# M_2_CSI2.net
KiCad netlist of a schematic drawn in Altium Designer
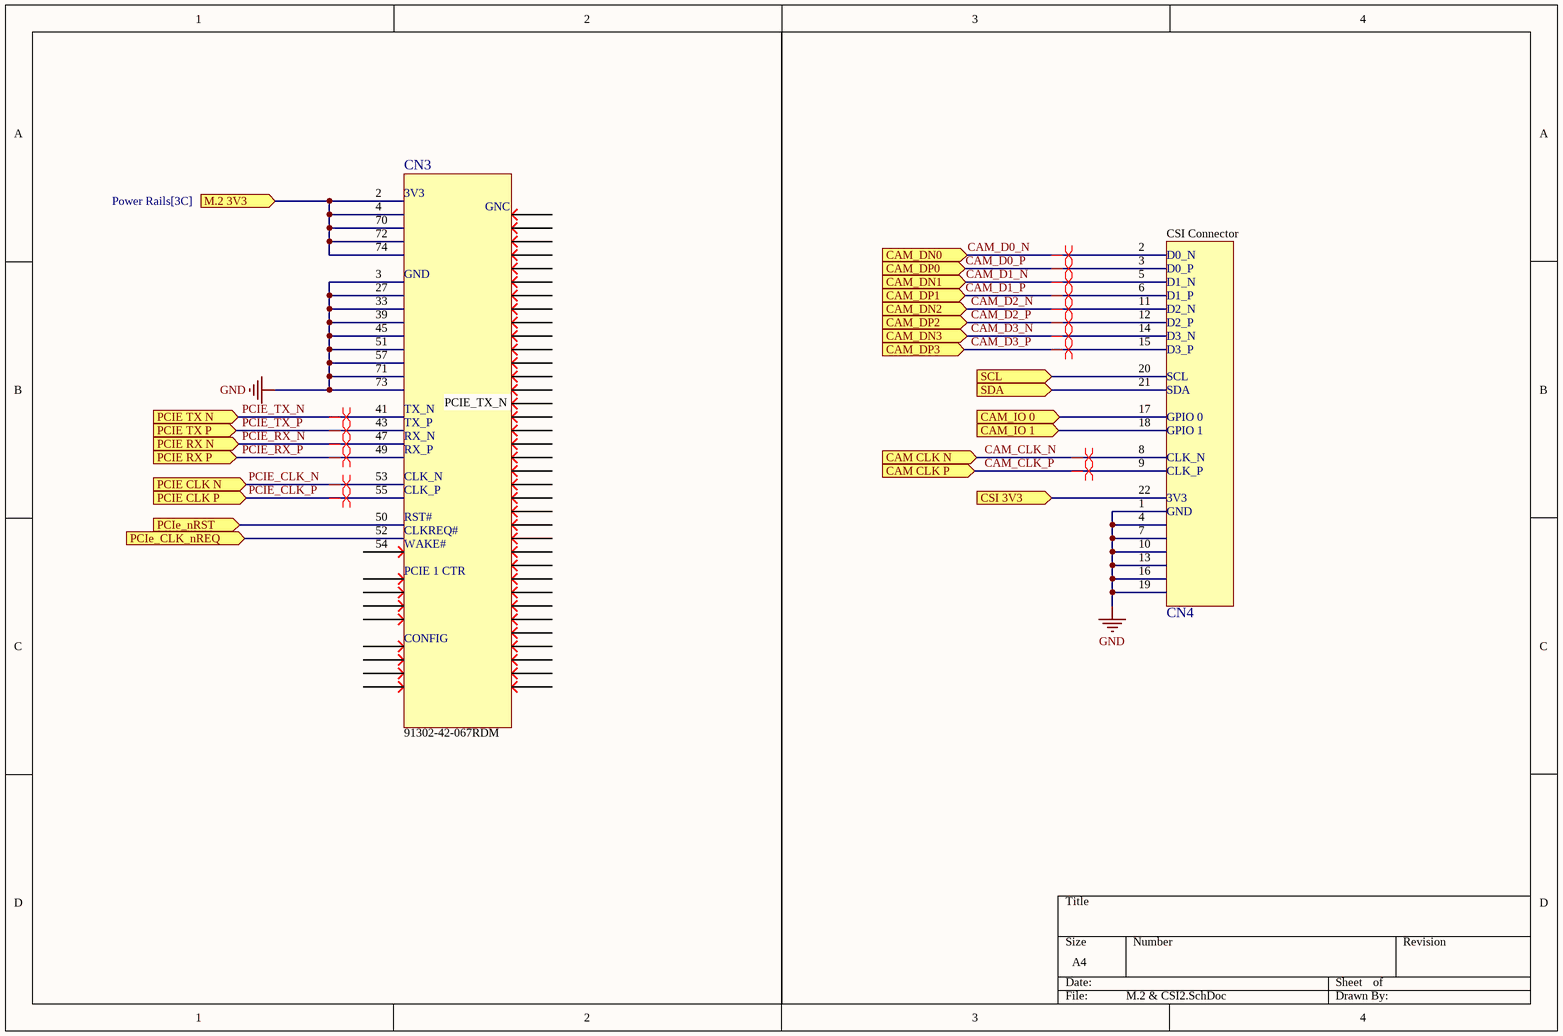
[diagram p0: M.2 & CSI2.SchDoc]

(export (version "E")
  (design (tool "Eeschema 10.0.6"))
  (components
    (comp (ref "CN3")
      (value "91302-42-067RDM")
      (footprint "CONN-SMD_91302-32-067RDM")
      (description "67P Surface Mount, Right Angle SMD,P=0.5mm Centronics Connectors RoHS")
      (fields (field (name "SOURCE") "LCSC"))
      (libsource (lib "C601195") (part "91302-42-067RDM"))
    )
    (comp (ref "CN4")
      (value "CSI Connector")
      (footprint "FPC-SMD_22P-P0.50_FH55-22S-0.5SH")
      (fields (field (name "SOURCE") "LCSC"))
      (libsource (lib "C5182313") (part "FH55-22S-0.5SH"))
    )
  )
  (nets
    (net (code "1") (name "/CAM_CLK_N") (class "Default")
      (node (ref "CN4") (pin "8") (pinfunction "CLK_N_8") (pintype "passive"))
    )
    (net (code "2") (name "/CAM_CLK_P") (class "Default")
      (node (ref "CN4") (pin "9") (pinfunction "CLK_P_9") (pintype "passive"))
    )
    (net (code "3") (name "/CAM_D0_N") (class "Default")
      (node (ref "CN4") (pin "2") (pinfunction "DATA_0_N_2") (pintype "passive"))
    )
    (net (code "4") (name "/CAM_D0_P") (class "Default")
      (node (ref "CN4") (pin "3") (pinfunction "DATA_0_P_3") (pintype "passive"))
    )
    (net (code "5") (name "/CAM_D1_N") (class "Default")
      (node (ref "CN4") (pin "5") (pinfunction "DATA_1_N_5") (pintype "passive"))
    )
    (net (code "6") (name "/CAM_D1_P") (class "Default")
      (node (ref "CN4") (pin "6") (pinfunction "DATA_1_P_6") (pintype "passive"))
    )
    (net (code "7") (name "/CAM_D2_N") (class "Default")
      (node (ref "CN4") (pin "11") (pinfunction "DATA_2_N_11") (pintype "passive"))
    )
    (net (code "8") (name "/CAM_D2_P") (class "Default")
      (node (ref "CN4") (pin "12") (pinfunction "DATA_2_P_12") (pintype "passive"))
    )
    (net (code "9") (name "/CAM_D3_N") (class "Default")
      (node (ref "CN4") (pin "14") (pinfunction "DATA_3_N_14") (pintype "passive"))
    )
    (net (code "10") (name "/CAM_D3_P") (class "Default")
      (node (ref "CN4") (pin "15") (pinfunction "DATA_3_P_15") (pintype "passive"))
    )
    (net (code "11") (name "/CAM_IO 0") (class "Default")
      (node (ref "CN4") (pin "17") (pinfunction "GPIO_0_17") (pintype "passive"))
    )
    (net (code "12") (name "/CAM_IO 1") (class "Default")
      (node (ref "CN4") (pin "18") (pinfunction "GPIO_1_18") (pintype "passive"))
    )
    (net (code "13") (name "/CSI 3V3") (class "Default")
      (node (ref "CN4") (pin "22") (pinfunction "PWR_22") (pintype "passive"))
    )
    (net (code "14") (name "/M.2 3V3") (class "Default")
      (node (ref "CN3") (pin "2") (pinfunction "2_2") (pintype "passive"))
      (node (ref "CN3") (pin "4") (pinfunction "4_4") (pintype "passive"))
      (node (ref "CN3") (pin "70") (pinfunction "70_70") (pintype "passive"))
      (node (ref "CN3") (pin "72") (pinfunction "72_72") (pintype "passive"))
      (node (ref "CN3") (pin "74") (pinfunction "74_74") (pintype "passive"))
    )
    (net (code "15") (name "/PCIE_CLK_N") (class "Default")
      (node (ref "CN3") (pin "53") (pinfunction "53_53") (pintype "passive"))
    )
    (net (code "16") (name "/PCIE_CLK_P") (class "Default")
      (node (ref "CN3") (pin "55") (pinfunction "55_55") (pintype "passive"))
    )
    (net (code "17") (name "/PCIE_RX_N") (class "Default")
      (node (ref "CN3") (pin "47") (pinfunction "47_47") (pintype "passive"))
    )
    (net (code "18") (name "/PCIE_RX_P") (class "Default")
      (node (ref "CN3") (pin "49") (pinfunction "49_49") (pintype "passive"))
    )
    (net (code "19") (name "/PCIE_TX_N") (class "Default")
      (node (ref "CN3") (pin "41") (pinfunction "41_41") (pintype "passive"))
    )
    (net (code "20") (name "/PCIE_TX_P") (class "Default")
      (node (ref "CN3") (pin "43") (pinfunction "43_43") (pintype "passive"))
    )
    (net (code "21") (name "/PCIe_CLK_nREQ") (class "Default")
      (node (ref "CN3") (pin "52") (pinfunction "52_52") (pintype "passive"))
    )
    (net (code "22") (name "/PCIe_nRST") (class "Default")
      (node (ref "CN3") (pin "50") (pinfunction "50_50") (pintype "passive"))
    )
    (net (code "23") (name "/SCL") (class "Default")
      (node (ref "CN4") (pin "20") (pinfunction "SCL_20") (pintype "passive"))
    )
    (net (code "24") (name "/SDA") (class "Default")
      (node (ref "CN4") (pin "21") (pinfunction "SDA_21") (pintype "passive"))
    )
    (net (code "25") (name "GND") (class "Default")
      (node (ref "CN3") (pin "27") (pinfunction "27_27") (pintype "passive"))
      (node (ref "CN3") (pin "3") (pinfunction "3_3") (pintype "passive"))
      (node (ref "CN3") (pin "33") (pinfunction "33_33") (pintype "passive"))
      (node (ref "CN3") (pin "39") (pinfunction "39_39") (pintype "passive"))
      (node (ref "CN3") (pin "45") (pinfunction "45_45") (pintype "passive"))
      (node (ref "CN3") (pin "51") (pinfunction "51_51") (pintype "passive"))
      (node (ref "CN3") (pin "57") (pinfunction "57_57") (pintype "passive"))
      (node (ref "CN3") (pin "71") (pinfunction "71_71") (pintype "passive"))
      (node (ref "CN3") (pin "73") (pinfunction "73_73") (pintype "passive"))
      (node (ref "CN4") (pin "1") (pinfunction "GND_1") (pintype "passive"))
      (node (ref "CN4") (pin "10") (pinfunction "GND_10") (pintype "passive"))
      (node (ref "CN4") (pin "13") (pinfunction "GND_13") (pintype "passive"))
      (node (ref "CN4") (pin "16") (pinfunction "GND_16") (pintype "passive"))
      (node (ref "CN4") (pin "19") (pinfunction "GND_19") (pintype "passive"))
      (node (ref "CN4") (pin "4") (pinfunction "GND_4") (pintype "passive"))
      (node (ref "CN4") (pin "7") (pinfunction "GND_7") (pintype "passive"))
    )
    (net (code "26") (name "unconnected-(CN3-Pad1)") (class "Default")
      (node (ref "CN3") (pin "1") (pinfunction "1_1") (pintype "passive+no_connect"))
    )
    (net (code "27") (name "unconnected-(CN3-Pad5)") (class "Default")
      (node (ref "CN3") (pin "5") (pinfunction "5_5") (pintype "passive+no_connect"))
    )
    (net (code "28") (name "unconnected-(CN3-Pad6)") (class "Default")
      (node (ref "CN3") (pin "6") (pinfunction "6_6") (pintype "passive+no_connect"))
    )
    (net (code "29") (name "unconnected-(CN3-Pad7)") (class "Default")
      (node (ref "CN3") (pin "7") (pinfunction "7_7") (pintype "passive+no_connect"))
    )
    (net (code "30") (name "unconnected-(CN3-Pad8)") (class "Default")
      (node (ref "CN3") (pin "8") (pinfunction "8_8") (pintype "passive+no_connect"))
    )
    (net (code "31") (name "unconnected-(CN3-Pad9)") (class "Default")
      (node (ref "CN3") (pin "9") (pinfunction "9_9") (pintype "passive+no_connect"))
    )
    (net (code "32") (name "unconnected-(CN3-Pad10)") (class "Default")
      (node (ref "CN3") (pin "10") (pinfunction "10_10") (pintype "passive+no_connect"))
    )
    (net (code "33") (name "unconnected-(CN3-Pad11)") (class "Default")
      (node (ref "CN3") (pin "11") (pinfunction "11_11") (pintype "passive+no_connect"))
    )
    (net (code "34") (name "unconnected-(CN3-Pad12)") (class "Default")
      (node (ref "CN3") (pin "12") (pinfunction "12_12") (pintype "passive+no_connect"))
    )
    (net (code "35") (name "unconnected-(CN3-Pad13)") (class "Default")
      (node (ref "CN3") (pin "13") (pinfunction "13_13") (pintype "passive+no_connect"))
    )
    (net (code "36") (name "unconnected-(CN3-Pad14)") (class "Default")
      (node (ref "CN3") (pin "14") (pinfunction "14_14") (pintype "passive+no_connect"))
    )
    (net (code "37") (name "unconnected-(CN3-Pad15)") (class "Default")
      (node (ref "CN3") (pin "15") (pinfunction "15_15") (pintype "passive+no_connect"))
    )
    (net (code "38") (name "unconnected-(CN3-Pad16)") (class "Default")
      (node (ref "CN3") (pin "16") (pinfunction "16_16") (pintype "passive+no_connect"))
    )
    (net (code "39") (name "unconnected-(CN3-Pad17)") (class "Default")
      (node (ref "CN3") (pin "17") (pinfunction "17_17") (pintype "passive+no_connect"))
    )
    (net (code "40") (name "unconnected-(CN3-Pad18)") (class "Default")
      (node (ref "CN3") (pin "18") (pinfunction "18_18") (pintype "passive+no_connect"))
    )
    (net (code "41") (name "unconnected-(CN3-Pad19)") (class "Default")
      (node (ref "CN3") (pin "19") (pinfunction "19_19") (pintype "passive+no_connect"))
    )
    (net (code "42") (name "unconnected-(CN3-Pad20)") (class "Default")
      (node (ref "CN3") (pin "20") (pinfunction "20_20") (pintype "passive+no_connect"))
    )
    (net (code "43") (name "unconnected-(CN3-Pad21)") (class "Default")
      (node (ref "CN3") (pin "21") (pinfunction "21_21") (pintype "passive+no_connect"))
    )
    (net (code "44") (name "unconnected-(CN3-Pad22)") (class "Default")
      (node (ref "CN3") (pin "22") (pinfunction "22_22") (pintype "passive+no_connect"))
    )
    (net (code "45") (name "unconnected-(CN3-Pad23)") (class "Default")
      (node (ref "CN3") (pin "23") (pinfunction "23_23") (pintype "passive+no_connect"))
    )
    (net (code "46") (name "unconnected-(CN3-Pad24)") (class "Default")
      (node (ref "CN3") (pin "24") (pinfunction "24_24") (pintype "passive+no_connect"))
    )
    (net (code "47") (name "unconnected-(CN3-Pad25)") (class "Default")
      (node (ref "CN3") (pin "25") (pinfunction "25_25") (pintype "passive+no_connect"))
    )
    (net (code "48") (name "unconnected-(CN3-Pad26)") (class "Default")
      (node (ref "CN3") (pin "26") (pinfunction "26_26") (pintype "passive+no_connect"))
    )
    (net (code "49") (name "unconnected-(CN3-Pad28)") (class "Default")
      (node (ref "CN3") (pin "28") (pinfunction "28_28") (pintype "passive+no_connect"))
    )
    (net (code "50") (name "unconnected-(CN3-Pad29)") (class "Default")
      (node (ref "CN3") (pin "29") (pinfunction "29_29") (pintype "passive+no_connect"))
    )
    (net (code "51") (name "unconnected-(CN3-Pad30)") (class "Default")
      (node (ref "CN3") (pin "30") (pinfunction "30_30") (pintype "passive+no_connect"))
    )
    (net (code "52") (name "unconnected-(CN3-Pad31)") (class "Default")
      (node (ref "CN3") (pin "31") (pinfunction "31_31") (pintype "passive+no_connect"))
    )
    (net (code "53") (name "unconnected-(CN3-Pad32)") (class "Default")
      (node (ref "CN3") (pin "32") (pinfunction "32_32") (pintype "passive+no_connect"))
    )
    (net (code "54") (name "unconnected-(CN3-Pad34)") (class "Default")
      (node (ref "CN3") (pin "34") (pinfunction "34_34") (pintype "passive+no_connect"))
    )
    (net (code "55") (name "unconnected-(CN3-Pad35)") (class "Default")
      (node (ref "CN3") (pin "35") (pinfunction "35_35") (pintype "passive+no_connect"))
    )
    (net (code "56") (name "unconnected-(CN3-Pad36)") (class "Default")
      (node (ref "CN3") (pin "36") (pinfunction "36_36") (pintype "passive+no_connect"))
    )
    (net (code "57") (name "unconnected-(CN3-Pad37)") (class "Default")
      (node (ref "CN3") (pin "37") (pinfunction "37_37") (pintype "passive+no_connect"))
    )
    (net (code "58") (name "unconnected-(CN3-Pad38)") (class "Default")
      (node (ref "CN3") (pin "38") (pinfunction "38_38") (pintype "passive+no_connect"))
    )
    (net (code "59") (name "unconnected-(CN3-Pad40)") (class "Default")
      (node (ref "CN3") (pin "40") (pinfunction "40_40") (pintype "passive+no_connect"))
    )
    (net (code "60") (name "unconnected-(CN3-Pad42)") (class "Default")
      (node (ref "CN3") (pin "42") (pinfunction "42_42") (pintype "passive+no_connect"))
    )
    (net (code "61") (name "unconnected-(CN3-Pad44)") (class "Default")
      (node (ref "CN3") (pin "44") (pinfunction "44_44") (pintype "passive+no_connect"))
    )
    (net (code "62") (name "unconnected-(CN3-Pad46)") (class "Default")
      (node (ref "CN3") (pin "46") (pinfunction "46_46") (pintype "passive+no_connect"))
    )
    (net (code "63") (name "unconnected-(CN3-Pad48)") (class "Default")
      (node (ref "CN3") (pin "48") (pinfunction "48_48") (pintype "passive+no_connect"))
    )
    (net (code "64") (name "unconnected-(CN3-Pad54)") (class "Default")
      (node (ref "CN3") (pin "54") (pinfunction "54_54") (pintype "passive+no_connect"))
    )
    (net (code "65") (name "unconnected-(CN3-Pad56)") (class "Default")
      (node (ref "CN3") (pin "56") (pinfunction "56_56") (pintype "passive+no_connect"))
    )
    (net (code "66") (name "unconnected-(CN3-Pad58)") (class "Default")
      (node (ref "CN3") (pin "58") (pinfunction "58_58") (pintype "passive+no_connect"))
    )
    (net (code "67") (name "unconnected-(CN3-Pad67)") (class "Default")
      (node (ref "CN3") (pin "67") (pinfunction "67_67") (pintype "passive+no_connect"))
    )
    (net (code "68") (name "unconnected-(CN3-Pad68)") (class "Default")
      (node (ref "CN3") (pin "68") (pinfunction "68_68") (pintype "passive+no_connect"))
    )
    (net (code "69") (name "unconnected-(CN3-Pad69)") (class "Default")
      (node (ref "CN3") (pin "69") (pinfunction "69_69") (pintype "passive+no_connect"))
    )
    (net (code "70") (name "unconnected-(CN3-Pad75)") (class "Default")
      (node (ref "CN3") (pin "75") (pinfunction "75_75") (pintype "passive+no_connect"))
    )
  )
)
